# CH32F203C8T6-R1.net
KiCad netlist of a schematic drawn in Altium Designer
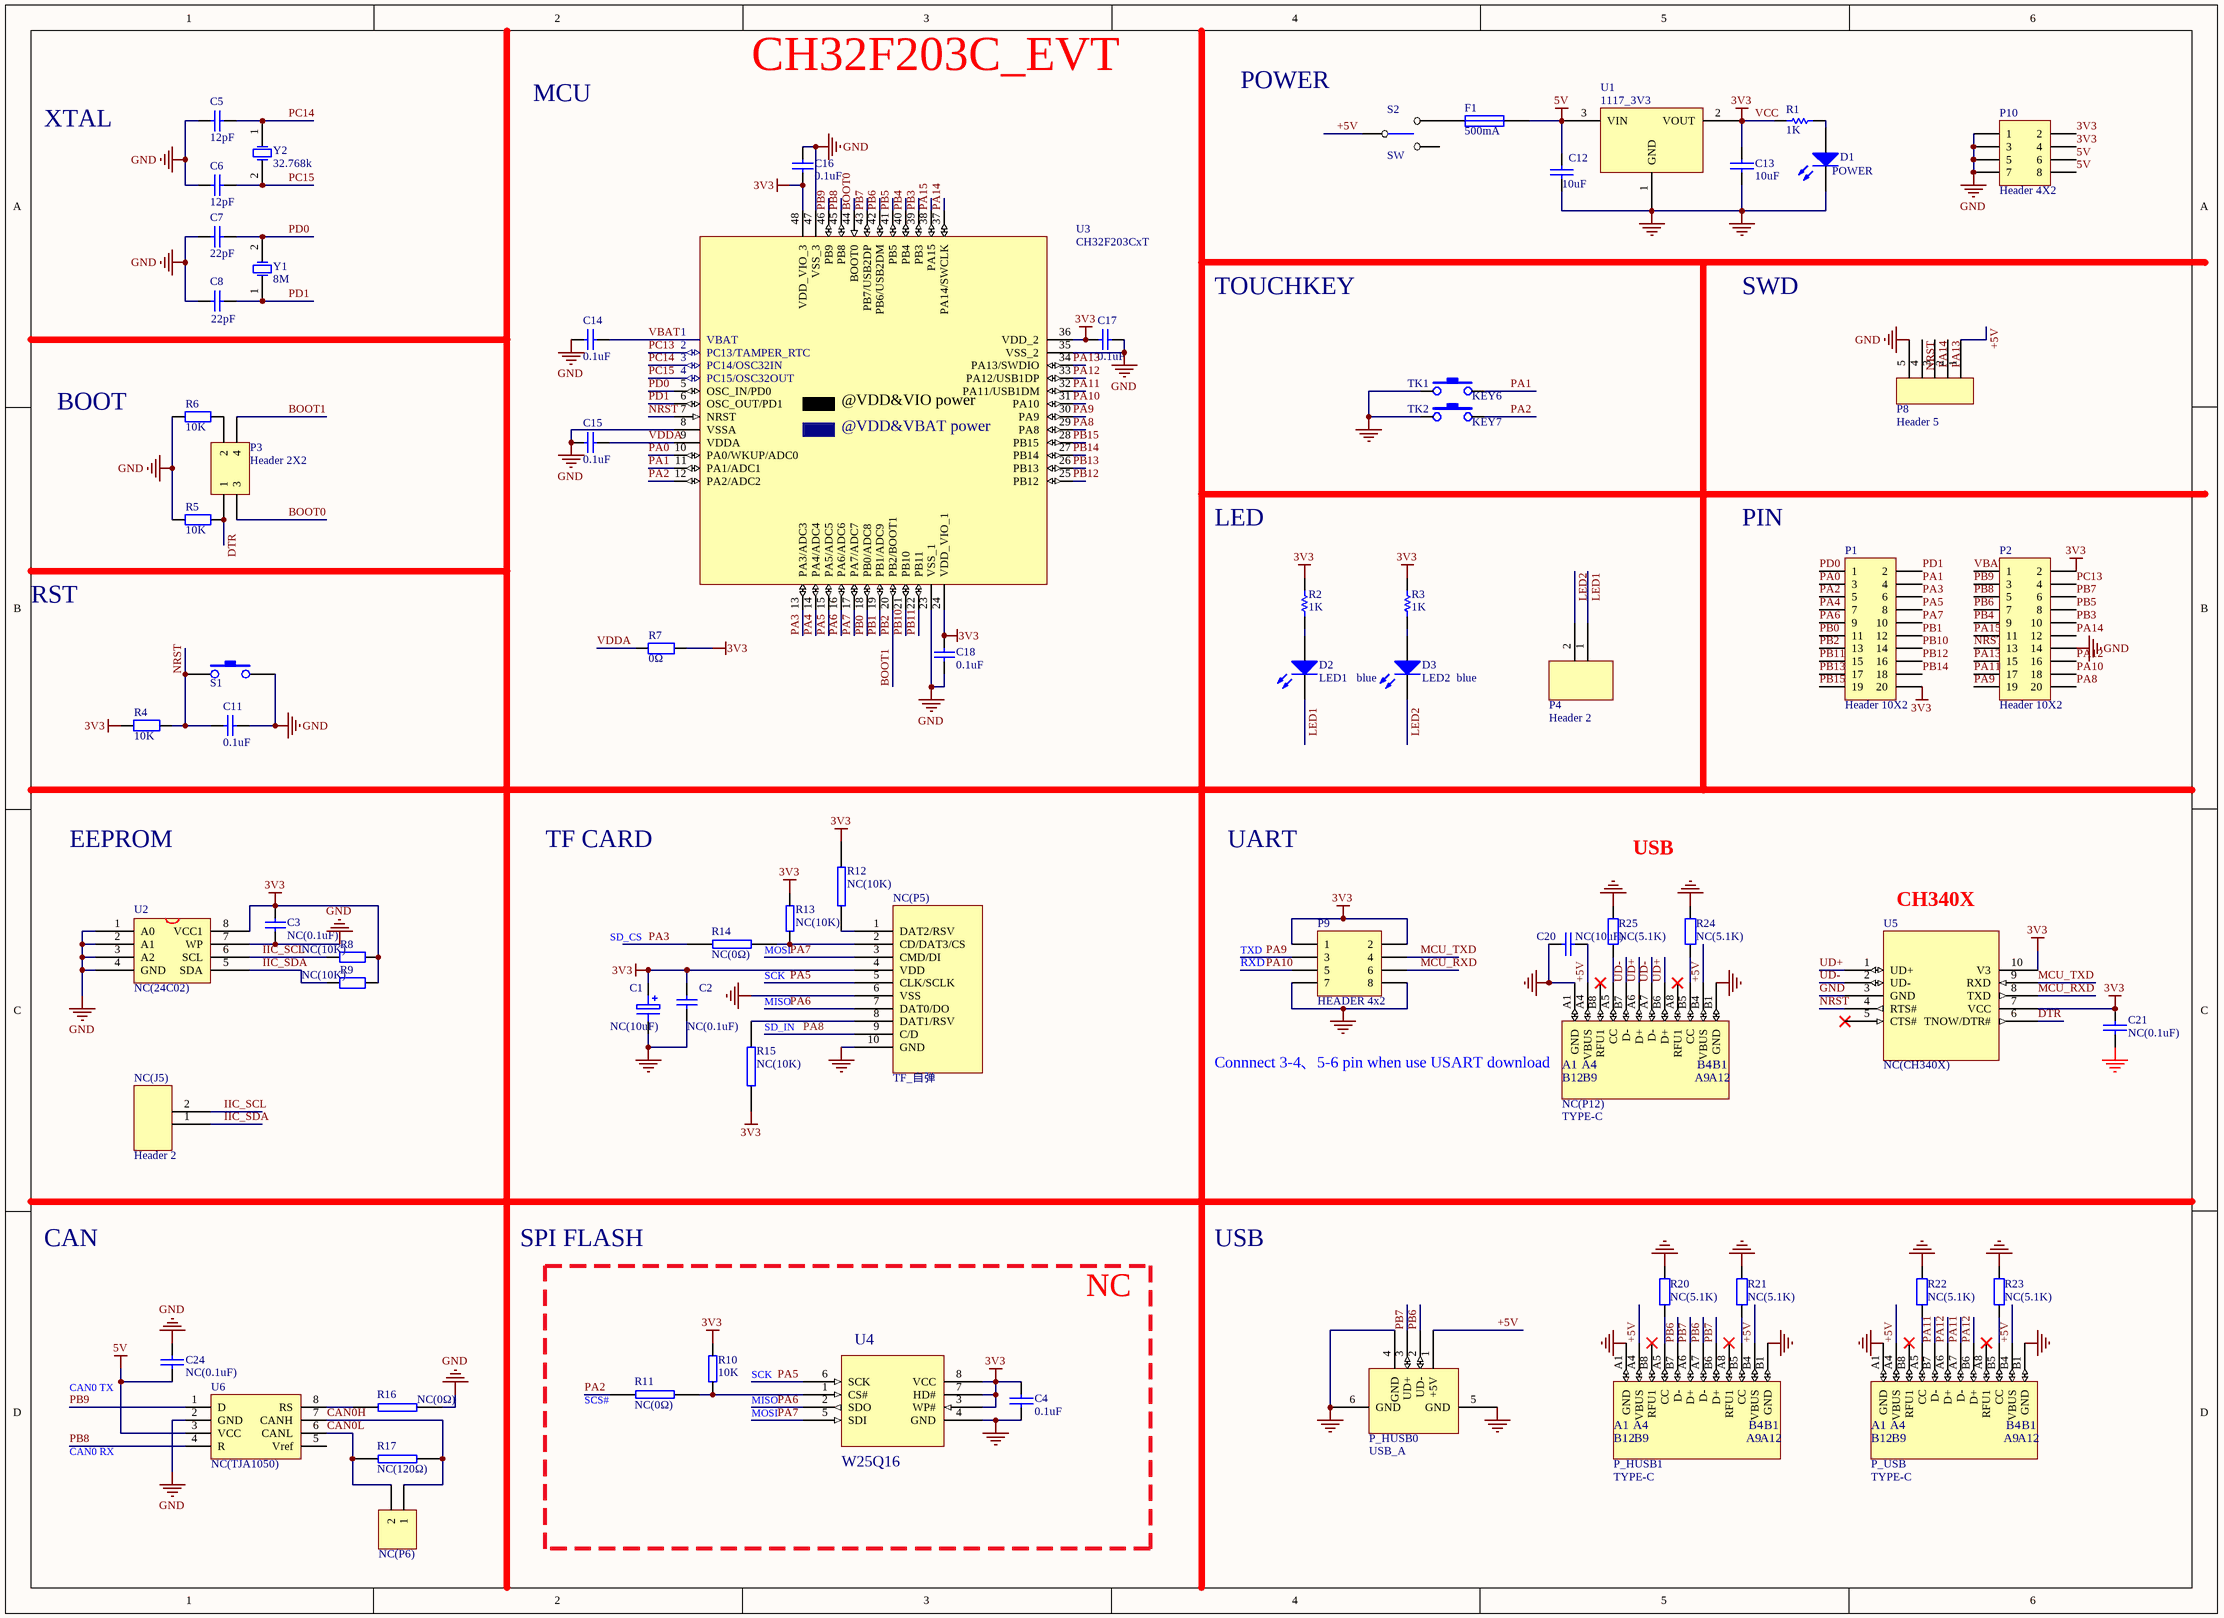
[diagram p0: CH32F203C8T6-R1.SchDoc]

(export (version "E")
  (design (tool "Eeschema 10.0.6"))
  (components
    (comp (ref "C1")
      (value "NC(10uF)")
      (footprint "3216")
      (description "Electrolytic Capacitor")
      (libsource (lib "*") (part "ELECTRO1"))
    )
    (comp (ref "C2")
      (value "NC(0.1uF)")
      (footprint "0603")
      (description "Capacitor")
      (fields (field (name "Comment") "0.1uF") (field (name "PUBLISHER") "Altium Limited"))
      (libsource (lib "*") (part "Cap"))
    )
    (comp (ref "C3")
      (value "NC(0.1uF)")
      (footprint "0603")
      (description "Capacitor")
      (fields (field (name "PUBLISHER") "Altium Limited"))
      (libsource (lib "Miscellaneous Devices") (part "Cap"))
    )
    (comp (ref "C4")
      (value "0.1uF")
      (footprint "0603")
      (description "Capacitor")
      (libsource (lib "") (part "CAP_1"))
    )
    (comp (ref "C5")
      (value "12pF")
      (footprint "0603")
      (description "Capacitor")
      (fields (field (name "PUBLISHER") "Altium Limited"))
      (libsource (lib "Miscellaneous Devices") (part "Cap"))
    )
    (comp (ref "C6")
      (value "12pF")
      (footprint "0603")
      (description "Capacitor")
      (fields (field (name "PUBLISHER") "Altium Limited"))
      (libsource (lib "Miscellaneous Devices") (part "Cap"))
    )
    (comp (ref "C7")
      (value "22pF")
      (footprint "0603")
      (description "Capacitor")
      (fields (field (name "PUBLISHER") "Altium Limited"))
      (libsource (lib "Miscellaneous Devices") (part "Cap"))
    )
    (comp (ref "C8")
      (value "22pF")
      (footprint "0603")
      (description "Capacitor")
      (fields (field (name "PUBLISHER") "Altium Limited"))
      (libsource (lib "Miscellaneous Devices") (part "Cap"))
    )
    (comp (ref "C11")
      (value "0.1uF")
      (footprint "0603")
      (description "Capacitor")
      (fields (field (name "PUBLISHER") "Altium Limited"))
      (libsource (lib "Miscellaneous Devices") (part "Cap"))
    )
    (comp (ref "C12")
      (value "10uF")
      (footprint "3216")
      (description "Capacitor")
      (libsource (lib "*") (part "CAP"))
    )
    (comp (ref "C13")
      (value "10uF")
      (footprint "0603")
      (description "Capacitor")
      (libsource (lib "*") (part "CAP"))
    )
    (comp (ref "C14")
      (value "0.1uF")
      (footprint "0603")
      (description "Capacitor")
      (fields (field (name "PUBLISHER") "Altium Limited"))
      (libsource (lib "Miscellaneous Devices") (part "Cap"))
    )
    (comp (ref "C15")
      (value "0.1uF")
      (footprint "0603")
      (description "Capacitor")
      (fields (field (name "PUBLISHER") "Altium Limited"))
      (libsource (lib "Miscellaneous Devices") (part "Cap"))
    )
    (comp (ref "C16")
      (value "0.1uF")
      (footprint "0603")
      (description "Capacitor")
      (fields (field (name "PUBLISHER") "Altium Limited"))
      (libsource (lib "Miscellaneous Devices") (part "Cap"))
    )
    (comp (ref "C17")
      (value "0.1uF")
      (footprint "0603")
      (description "Capacitor")
      (fields (field (name "PUBLISHER") "Altium Limited"))
      (libsource (lib "Miscellaneous Devices") (part "Cap"))
    )
    (comp (ref "C18")
      (value "0.1uF")
      (footprint "0603")
      (description "Capacitor")
      (fields (field (name "PUBLISHER") "Altium Limited"))
      (libsource (lib "Miscellaneous Devices") (part "Cap"))
    )
    (comp (ref "C20")
      (value "NC(10uF)")
      (footprint "3216_C")
      (description "Capacitor")
      (libsource (lib "*") (part "CAP"))
    )
    (comp (ref "C21")
      (value "NC(0.1uF)")
      (footprint "0603_C")
      (description "Capacitor")
      (libsource (lib "*") (part "CAP"))
    )
    (comp (ref "C24")
      (value "NC(0.1uF)")
      (footprint "0603")
      (description "Capacitor")
      (libsource (lib "") (part "CAP_1"))
    )
    (comp (ref "D1")
      (value "POWER")
      (footprint "0603L")
      (description "Typical INFRARED GaAs LED")
      (fields (field (name "PUBLISHER") "Altium Limited"))
      (libsource (lib "Miscellaneous Devices") (part "LED0"))
    )
    (comp (ref "D2")
      (value "LED1   blue")
      (footprint "0603L")
      (description "Typical INFRARED GaAs LED")
      (fields (field (name "PUBLISHER") "Altium Limited"))
      (libsource (lib "Miscellaneous Devices") (part "LED0"))
    )
    (comp (ref "D3")
      (value "LED2  blue")
      (footprint "0603L")
      (description "Typical INFRARED GaAs LED")
      (fields (field (name "PUBLISHER") "Altium Limited"))
      (libsource (lib "Miscellaneous Devices") (part "LED0"))
    )
    (comp (ref "F1")
      (value "500mA")
      (footprint "0603")
      (description "Fuse")
      (libsource (lib "*") (part "FUSE1"))
    )
    (comp (ref "NC(J5)")
      (value "Header 2")
      (footprint "SIP2 - 40mil")
      (libsource (lib "MYSCH") (part "2HEAD"))
    )
    (comp (ref "NC(P5)") (value "TF_自弹") (footprint "TF_CARD") (libsource (lib "*") (part "TF_自弹")))
    (comp (ref "NC(P6)")
      (value "Header 2")
      (footprint "PORT2 4.5MM")
      (description "Header, 2-Pin")
      (fields (field (name "PUBLISHER") "Altium Limited"))
      (libsource (lib "Miscellaneous Connectors") (part "Header 2"))
    )
    (comp (ref "NC(P12)")
      (value "TYPE-C")
      (footprint "TYPE-C-Receptacle-2.0")
      (libsource (lib "*") (part "TYPE-C1"))
    )
    (comp (ref "P1")
      (value "Header 10X2")
      (footprint "IDC20")
      (description "Header, 10-Pin, Dual row")
      (fields (field (name "PUBLISHER") "Altium Limited"))
      (libsource (lib "Miscellaneous Connectors") (part "Header 10X2"))
    )
    (comp (ref "P2")
      (value "Header 10X2")
      (footprint "IDC20")
      (description "Header, 10-Pin, Dual row")
      (fields (field (name "PUBLISHER") "Altium Limited"))
      (libsource (lib "Miscellaneous Connectors") (part "Header 10X2"))
    )
    (comp (ref "P3")
      (value "Header 2X2")
      (footprint "HDR2X2")
      (description "Header, 2-Pin, Dual row")
      (fields (field (name "PUBLISHER") "Altium Limited"))
      (libsource (lib "Miscellaneous Connectors") (part "Header 2X2"))
    )
    (comp (ref "P4") (value "Header 2") (footprint "SIP2 - 40mil") (libsource (lib "") (part "2HEAD_1")))
    (comp (ref "P8")
      (value "Header 5")
      (footprint "SIP5 - 40mil")
      (libsource (lib "PCB_Project1") (part "2HEAD"))
    )
    (comp (ref "P9")
      (value "HEADER 4x2")
      (footprint "MYPCB:IDC8-2.54mm")
      (description "Header, 4-Pin, Dual row")
      (libsource (lib "wch_sch_others") (part "HEADER 4x2"))
    )
    (comp (ref "P10")
      (value "Header 4X2")
      (footprint "IDC8")
      (description "Header, 4-Pin, Dual row")
      (fields (field (name "PUBLISHER") "Altium Limited"))
      (libsource (lib "Miscellaneous Connectors") (part "Header 4X2"))
    )
    (comp (ref "P_HUSB0")
      (value "USB_A")
      (footprint "USBA-l")
      (description "USB Port")
      (libsource (lib "CHXXXSCH") (part "USB"))
    )
    (comp (ref "P_HUSB1")
      (value "TYPE-C")
      (footprint "TYPE-C-Receptacle-2.0")
      (libsource (lib "*") (part "TYPE-C1"))
    )
    (comp (ref "P_USB")
      (value "TYPE-C")
      (footprint "TYPE-C-Receptacle-2.0")
      (libsource (lib "*") (part "TYPE-C1"))
    )
    (comp (ref "R1")
      (value "1K")
      (footprint "0603")
      (description "Semiconductor Resistor")
      (fields (field (name "PUBLISHER") "Altium Limited"))
      (libsource (lib "Miscellaneous Devices") (part "Res Semi"))
    )
    (comp (ref "R2")
      (value "1K")
      (footprint "0603")
      (description "Semiconductor Resistor")
      (fields (field (name "PUBLISHER") "Altium Limited"))
      (libsource (lib "Miscellaneous Devices") (part "Res Semi"))
    )
    (comp (ref "R3")
      (value "1K")
      (footprint "0603")
      (description "Semiconductor Resistor")
      (fields (field (name "PUBLISHER") "Altium Limited"))
      (libsource (lib "Miscellaneous Devices") (part "Res Semi"))
    )
    (comp (ref "R4")
      (value "10K")
      (footprint "0603")
      (description "Resistor")
      (fields (field (name "PUBLISHER") "Altium Limited"))
      (libsource (lib "Miscellaneous Devices") (part "Res2"))
    )
    (comp (ref "R5")
      (value "10K")
      (footprint "0603")
      (description "Resistor")
      (fields (field (name "PUBLISHER") "Altium Limited"))
      (libsource (lib "Miscellaneous Devices") (part "Res2"))
    )
    (comp (ref "R6")
      (value "10K")
      (footprint "0603")
      (description "Resistor")
      (fields (field (name "PUBLISHER") "Altium Limited"))
      (libsource (lib "Miscellaneous Devices") (part "Res2"))
    )
    (comp (ref "R7")
      (value "0Ω")
      (footprint "0603")
      (description "Resistor")
      (fields (field (name "PUBLISHER") "Altium Limited"))
      (libsource (lib "Miscellaneous Devices") (part "Res2"))
    )
    (comp (ref "R8")
      (value "NC(10K)")
      (footprint "0603")
      (description "Resistor")
      (fields (field (name "PUBLISHER") "Altium Limited"))
      (libsource (lib "Miscellaneous Devices") (part "Res2"))
    )
    (comp (ref "R9")
      (value "NC(10K)")
      (footprint "0603")
      (description "Resistor")
      (fields (field (name "PUBLISHER") "Altium Limited"))
      (libsource (lib "Miscellaneous Devices") (part "Res2"))
    )
    (comp (ref "R10") (value "10K") (footprint "0603") (libsource (lib "*") (part "DZ")))
    (comp (ref "R11") (value "NC(0Ω)") (footprint "0603") (libsource (lib "*") (part "RES2")))
    (comp (ref "R12") (value "NC(10K)") (footprint "0603") (libsource (lib "*") (part "RES2")))
    (comp (ref "R13") (value "NC(10K)") (footprint "0603") (libsource (lib "*") (part "DZ")))
    (comp (ref "R14") (value "NC(0Ω)") (footprint "0603") (libsource (lib "*") (part "RES2")))
    (comp (ref "R15") (value "NC(10K)") (footprint "0603") (libsource (lib "*") (part "RES2")))
    (comp (ref "R16") (value "NC(0Ω)") (footprint "0603") (libsource (lib "*") (part "RES2")))
    (comp (ref "R17") (value "NC(120Ω)") (footprint "0603") (libsource (lib "*") (part "RES2")))
    (comp (ref "R20")
      (value "NC(5.1K)")
      (footprint "0603")
      (description "Resistor")
      (libsource (lib "") (part "Res2_1"))
    )
    (comp (ref "R21")
      (value "NC(5.1K)")
      (footprint "0603")
      (description "Resistor")
      (libsource (lib "") (part "Res2_1"))
    )
    (comp (ref "R22")
      (value "NC(5.1K)")
      (footprint "0603")
      (description "Resistor")
      (libsource (lib "") (part "Res2_1"))
    )
    (comp (ref "R23")
      (value "NC(5.1K)")
      (footprint "0603")
      (description "Resistor")
      (libsource (lib "") (part "Res2_1"))
    )
    (comp (ref "R24")
      (value "NC(5.1K)")
      (footprint "0603")
      (description "Resistor")
      (libsource (lib "") (part "Res2_1"))
    )
    (comp (ref "R25")
      (value "NC(5.1K)")
      (footprint "0603")
      (description "Resistor")
      (libsource (lib "") (part "Res2_1"))
    )
    (comp (ref "S1") (value "KEY") (footprint "贴片按键") (libsource (lib "CCDXPLIB") (part "KEY")))
    (comp (ref "S2") (value "SW") (footprint "KEY2") (libsource (lib "MYSCH") (part "SW")))
    (comp (ref "TK1") (value "KEY6") (footprint "KEY68") (libsource (lib "*") (part "KEY")))
    (comp (ref "TK2") (value "KEY7") (footprint "KEY68") (libsource (lib "*") (part "KEY")))
    (comp (ref "U1") (value "1117_3V3") (footprint "SOT-223") (libsource (lib "*") (part "LM1117_3.3V")))
    (comp (ref "U2") (value "NC(24C02)") (footprint "SOP8") (libsource (lib "Elite_SCH") (part "24C256")))
    (comp (ref "U3")
      (value "CH32F203CxT")
      (footprint "LQFP48")
      (description "ARM M3 LMD-MCU, 144MHz, 2*USB FS, CAN")
      (libsource (lib "CHXXX") (part "CH32F203CxT"))
    )
    (comp (ref "U4")
      (value "W25Q16")
      (footprint "016 SO-8")
      (libsource (lib "*") (part "Pro89C.tmp_25F512_2"))
    )
    (comp (ref "U5")
      (value "NC(CH340X)")
      (footprint "MSOP10")
      (description "USB to TTL Serial / UART")
      (libsource (lib "CHXXX") (part "CH340X"))
    )
    (comp (ref "U6") (value "NC(TJA1050)") (footprint "SOP8") (libsource (lib "CAN") (part "Component_1")))
    (comp (ref "Y1")
      (value "8M")
      (footprint "XT62/28")
      (description "Crystal Oscillator")
      (fields (field (name "PUBLISHER") "Altium Limited"))
      (libsource (lib "Miscellaneous Devices") (part "XTAL"))
    )
    (comp (ref "Y2")
      (value "32.768k")
      (footprint "FC-135")
      (description "Crystal Oscillator")
      (fields (field (name "PUBLISHER") "Altium Limited"))
      (libsource (lib "Miscellaneous Devices") (part "XTAL"))
    )
  )
  (nets
    (net (code "1") (name "/+5V") (class "Default")
      (node (ref "C20") (pin "2") (pinfunction "2_2") (pintype "passive"))
      (node (ref "NC(P12)") (pin "A4") (pinfunction "VBUS_A4") (pintype "bidirectional"))
      (node (ref "NC(P12)") (pin "B4") (pinfunction "VBUS_B4") (pintype "bidirectional"))
      (node (ref "P8") (pin "1") (pintype "passive"))
      (node (ref "P_HUSB0") (pin "1") (pinfunction "+5V_1") (pintype "power_in"))
      (node (ref "P_HUSB1") (pin "A4") (pinfunction "VBUS_A4") (pintype "bidirectional"))
      (node (ref "P_HUSB1") (pin "B4") (pinfunction "VBUS_B4") (pintype "bidirectional"))
      (node (ref "P_USB") (pin "A4") (pinfunction "VBUS_A4") (pintype "bidirectional"))
      (node (ref "P_USB") (pin "B4") (pinfunction "VBUS_B4") (pintype "bidirectional"))
      (node (ref "S2") (pin "1") (pinfunction "1_1") (pintype "passive"))
    )
    (net (code "3") (name "/BOOT0") (class "Default")
      (node (ref "P3") (pin "3") (pinfunction "3_3") (pintype "passive"))
      (node (ref "U3") (pin "44") (pinfunction "BOOT0_44") (pintype "input"))
    )
    (net (code "4") (name "/BOOT1") (class "Default")
      (node (ref "P1") (pin "13") (pinfunction "13_13") (pintype "passive"))
      (node (ref "P3") (pin "4") (pinfunction "4_4") (pintype "passive"))
      (node (ref "U3") (pin "20") (pinfunction "PB2/BOOT1_20") (pintype "bidirectional"))
    )
    (net (code "5") (name "/CAN0H") (class "Default")
      (node (ref "NC(P6)") (pin "1") (pinfunction "1_1") (pintype "passive"))
      (node (ref "R17") (pin "1") (pinfunction "1_1") (pintype "passive"))
      (node (ref "U6") (pin "7") (pinfunction "CANH_7") (pintype "passive"))
    )
    (net (code "6") (name "/CAN0L") (class "Default")
      (node (ref "NC(P6)") (pin "2") (pinfunction "2_2") (pintype "passive"))
      (node (ref "R17") (pin "2") (pinfunction "2_2") (pintype "passive"))
      (node (ref "U6") (pin "6") (pinfunction "CANL_6") (pintype "passive"))
    )
    (net (code "7") (name "/DTR") (class "Default")
      (node (ref "P3") (pin "1") (pinfunction "1_1") (pintype "passive"))
      (node (ref "R5") (pin "1") (pinfunction "1_1") (pintype "passive"))
      (node (ref "U5") (pin "6") (pinfunction "TNOW/DTR#_6") (pintype "output"))
    )
    (net (code "8") (name "/IIC_SCL") (class "Default")
      (node (ref "NC(J5)") (pin "2") (pintype "passive"))
      (node (ref "R8") (pin "2") (pinfunction "2_2") (pintype "passive"))
      (node (ref "U2") (pin "6") (pinfunction "SCL_6") (pintype "passive"))
    )
    (net (code "9") (name "/IIC_SDA") (class "Default")
      (node (ref "NC(J5)") (pin "1") (pintype "passive"))
      (node (ref "R9") (pin "2") (pinfunction "2_2") (pintype "passive"))
      (node (ref "U2") (pin "5") (pinfunction "SDA_5") (pintype "passive"))
    )
    (net (code "10") (name "/LED1") (class "Default")
      (node (ref "D2") (pin "2") (pinfunction "K_2") (pintype "passive"))
      (node (ref "P4") (pin "1") (pintype "passive"))
    )
    (net (code "11") (name "/LED2") (class "Default")
      (node (ref "D3") (pin "2") (pinfunction "K_2") (pintype "passive"))
      (node (ref "P4") (pin "2") (pintype "passive"))
    )
    (net (code "12") (name "/MCU_RXD") (class "Default")
      (node (ref "P9") (pin "6") (pinfunction "6_6") (pintype "passive"))
      (node (ref "U5") (pin "8") (pinfunction "TXD_8") (pintype "output"))
    )
    (net (code "13") (name "/MCU_TXD") (class "Default")
      (node (ref "P9") (pin "4") (pinfunction "4_4") (pintype "passive"))
      (node (ref "U5") (pin "9") (pinfunction "RXD_9") (pintype "input"))
    )
    (net (code "14") (name "/NRST") (class "Default")
      (node (ref "C11") (pin "2") (pinfunction "2_2") (pintype "passive"))
      (node (ref "P2") (pin "13") (pinfunction "13_13") (pintype "passive"))
      (node (ref "P8") (pin "4") (pintype "passive"))
      (node (ref "R4") (pin "1") (pinfunction "1_1") (pintype "passive"))
      (node (ref "S1") (pin "1") (pinfunction "1_1") (pintype "passive"))
      (node (ref "U3") (pin "7") (pinfunction "NRST_7") (pintype "input"))
      (node (ref "U5") (pin "4") (pinfunction "RTS#_4") (pintype "output"))
    )
    (net (code "15") (name "/PA0") (class "Default")
      (node (ref "P1") (pin "3") (pinfunction "3_3") (pintype "passive"))
      (node (ref "U3") (pin "10") (pinfunction "PA0/WKUP/ADC0_10") (pintype "bidirectional"))
    )
    (net (code "16") (name "/PA1") (class "Default")
      (node (ref "P1") (pin "4") (pinfunction "4_4") (pintype "passive"))
      (node (ref "TK1") (pin "1") (pintype "passive"))
      (node (ref "U3") (pin "11") (pinfunction "PA1/ADC1_11") (pintype "bidirectional"))
    )
    (net (code "17") (name "/PA2") (class "Default")
      (node (ref "P1") (pin "5") (pinfunction "5_5") (pintype "passive"))
      (node (ref "R11") (pin "2") (pinfunction "2_2") (pintype "passive"))
      (node (ref "TK2") (pin "1") (pintype "passive"))
      (node (ref "U3") (pin "12") (pinfunction "PA2/ADC2_12") (pintype "bidirectional"))
    )
    (net (code "18") (name "/PA3") (class "Default")
      (node (ref "P1") (pin "6") (pinfunction "6_6") (pintype "passive"))
      (node (ref "R14") (pin "2") (pinfunction "2_2") (pintype "passive"))
      (node (ref "U3") (pin "13") (pinfunction "PA3/ADC3_13") (pintype "bidirectional"))
    )
    (net (code "19") (name "/PA4") (class "Default")
      (node (ref "P1") (pin "7") (pinfunction "7_7") (pintype "passive"))
      (node (ref "U3") (pin "14") (pinfunction "PA4/ADC4_14") (pintype "bidirectional"))
    )
    (net (code "20") (name "/PA5") (class "Default")
      (node (ref "NC(P5)") (pin "5") (pinfunction "CLK/SCLK_5") (pintype "passive"))
      (node (ref "P1") (pin "8") (pinfunction "8_8") (pintype "passive"))
      (node (ref "U3") (pin "15") (pinfunction "PA5/ADC5_15") (pintype "bidirectional"))
      (node (ref "U4") (pin "6") (pinfunction "SCK_6") (pintype "input"))
    )
    (net (code "21") (name "/PA6") (class "Default")
      (node (ref "NC(P5)") (pin "7") (pinfunction "DAT0/DO_7") (pintype "passive"))
      (node (ref "P1") (pin "9") (pinfunction "9_9") (pintype "passive"))
      (node (ref "U3") (pin "16") (pinfunction "PA6/ADC6_16") (pintype "bidirectional"))
      (node (ref "U4") (pin "2") (pinfunction "SDO_2") (pintype "output"))
    )
    (net (code "22") (name "/PA7") (class "Default")
      (node (ref "NC(P5)") (pin "3") (pinfunction "CMD/DI_3") (pintype "passive"))
      (node (ref "P1") (pin "10") (pinfunction "10_10") (pintype "passive"))
      (node (ref "U3") (pin "17") (pinfunction "PA7/ADC7_17") (pintype "bidirectional"))
      (node (ref "U4") (pin "5") (pinfunction "SDI_5") (pintype "input"))
    )
    (net (code "23") (name "/PA8") (class "Default")
      (node (ref "NC(P5)") (pin "9") (pinfunction "C/D_9") (pintype "passive"))
      (node (ref "P2") (pin "20") (pinfunction "20_20") (pintype "passive"))
      (node (ref "U3") (pin "29") (pinfunction "PA8_29") (pintype "bidirectional"))
    )
    (net (code "24") (name "/PA9") (class "Default")
      (node (ref "P2") (pin "19") (pinfunction "19_19") (pintype "passive"))
      (node (ref "P9") (pin "3") (pinfunction "3_3") (pintype "passive"))
      (node (ref "U3") (pin "30") (pinfunction "PA9_30") (pintype "bidirectional"))
    )
    (net (code "25") (name "/PA10") (class "Default")
      (node (ref "P2") (pin "18") (pinfunction "18_18") (pintype "passive"))
      (node (ref "P9") (pin "5") (pinfunction "5_5") (pintype "passive"))
      (node (ref "U3") (pin "31") (pinfunction "PA10_31") (pintype "bidirectional"))
    )
    (net (code "26") (name "/PA11") (class "Default")
      (node (ref "P2") (pin "17") (pinfunction "17_17") (pintype "passive"))
      (node (ref "P_USB") (pin "A7") (pinfunction "D-_A7") (pintype "bidirectional"))
      (node (ref "P_USB") (pin "B7") (pinfunction "D-_B7") (pintype "bidirectional"))
      (node (ref "U3") (pin "32") (pinfunction "PA11/USB1DM_32") (pintype "bidirectional"))
    )
    (net (code "27") (name "/PA12") (class "Default")
      (node (ref "P2") (pin "16") (pinfunction "16_16") (pintype "passive"))
      (node (ref "P_USB") (pin "A6") (pinfunction "D+_A6") (pintype "bidirectional"))
      (node (ref "P_USB") (pin "B6") (pinfunction "D+_B6") (pintype "bidirectional"))
      (node (ref "U3") (pin "33") (pinfunction "PA12/USB1DP_33") (pintype "bidirectional"))
    )
    (net (code "28") (name "/PA13") (class "Default")
      (node (ref "P2") (pin "15") (pinfunction "15_15") (pintype "passive"))
      (node (ref "P8") (pin "2") (pintype "passive"))
      (node (ref "U3") (pin "34") (pinfunction "PA13/SWDIO_34") (pintype "bidirectional"))
    )
    (net (code "29") (name "/PA14") (class "Default")
      (node (ref "P2") (pin "12") (pinfunction "12_12") (pintype "passive"))
      (node (ref "P8") (pin "3") (pintype "passive"))
      (node (ref "U3") (pin "37") (pinfunction "PA14/SWCLK_37") (pintype "bidirectional"))
    )
    (net (code "30") (name "/PA15") (class "Default")
      (node (ref "P2") (pin "11") (pinfunction "11_11") (pintype "passive"))
      (node (ref "U3") (pin "38") (pinfunction "PA15_38") (pintype "bidirectional"))
    )
    (net (code "31") (name "/PB0") (class "Default")
      (node (ref "P1") (pin "11") (pinfunction "11_11") (pintype "passive"))
      (node (ref "U3") (pin "18") (pinfunction "PB0/ADC8_18") (pintype "bidirectional"))
    )
    (net (code "32") (name "/PB1") (class "Default")
      (node (ref "P1") (pin "12") (pinfunction "12_12") (pintype "passive"))
      (node (ref "U3") (pin "19") (pinfunction "PB1/ADC9_19") (pintype "bidirectional"))
    )
    (net (code "33") (name "/PB3") (class "Default")
      (node (ref "P2") (pin "10") (pinfunction "10_10") (pintype "passive"))
      (node (ref "U3") (pin "39") (pinfunction "PB3_39") (pintype "bidirectional"))
    )
    (net (code "34") (name "/PB4") (class "Default")
      (node (ref "P2") (pin "9") (pinfunction "9_9") (pintype "passive"))
      (node (ref "U3") (pin "40") (pinfunction "PB4_40") (pintype "bidirectional"))
    )
    (net (code "35") (name "/PB5") (class "Default")
      (node (ref "P2") (pin "8") (pinfunction "8_8") (pintype "passive"))
      (node (ref "U3") (pin "41") (pinfunction "PB5_41") (pintype "bidirectional"))
    )
    (net (code "36") (name "/PB6") (class "Default")
      (node (ref "P2") (pin "7") (pinfunction "7_7") (pintype "passive"))
      (node (ref "P_HUSB0") (pin "2") (pinfunction "UD-_2") (pintype "bidirectional"))
      (node (ref "P_HUSB1") (pin "A7") (pinfunction "D-_A7") (pintype "bidirectional"))
      (node (ref "P_HUSB1") (pin "B7") (pinfunction "D-_B7") (pintype "bidirectional"))
      (node (ref "U3") (pin "42") (pinfunction "PB6/USB2DM_42") (pintype "bidirectional"))
    )
    (net (code "37") (name "/PB7") (class "Default")
      (node (ref "P2") (pin "6") (pinfunction "6_6") (pintype "passive"))
      (node (ref "P_HUSB0") (pin "3") (pinfunction "UD+_3") (pintype "bidirectional"))
      (node (ref "P_HUSB1") (pin "A6") (pinfunction "D+_A6") (pintype "bidirectional"))
      (node (ref "P_HUSB1") (pin "B6") (pinfunction "D+_B6") (pintype "bidirectional"))
      (node (ref "U3") (pin "43") (pinfunction "PB7/USB2DP_43") (pintype "bidirectional"))
    )
    (net (code "38") (name "/PB8") (class "Default")
      (node (ref "P2") (pin "5") (pinfunction "5_5") (pintype "passive"))
      (node (ref "U3") (pin "45") (pinfunction "PB8_45") (pintype "bidirectional"))
      (node (ref "U6") (pin "4") (pinfunction "R_4") (pintype "passive"))
    )
    (net (code "39") (name "/PB9") (class "Default")
      (node (ref "P2") (pin "3") (pinfunction "3_3") (pintype "passive"))
      (node (ref "U3") (pin "46") (pinfunction "PB9_46") (pintype "bidirectional"))
      (node (ref "U6") (pin "1") (pinfunction "D_1") (pintype "passive"))
    )
    (net (code "40") (name "/PB10") (class "Default")
      (node (ref "P1") (pin "14") (pinfunction "14_14") (pintype "passive"))
      (node (ref "U3") (pin "21") (pinfunction "PB10_21") (pintype "bidirectional"))
    )
    (net (code "41") (name "/PB11") (class "Default")
      (node (ref "P1") (pin "15") (pinfunction "15_15") (pintype "passive"))
      (node (ref "U3") (pin "22") (pinfunction "PB11_22") (pintype "bidirectional"))
    )
    (net (code "42") (name "/PB12") (class "Default")
      (node (ref "P1") (pin "16") (pinfunction "16_16") (pintype "passive"))
      (node (ref "U3") (pin "25") (pinfunction "PB12_25") (pintype "bidirectional"))
    )
    (net (code "43") (name "/PB13") (class "Default")
      (node (ref "P1") (pin "17") (pinfunction "17_17") (pintype "passive"))
      (node (ref "U3") (pin "26") (pinfunction "PB13_26") (pintype "bidirectional"))
    )
    (net (code "44") (name "/PB14") (class "Default")
      (node (ref "P1") (pin "18") (pinfunction "18_18") (pintype "passive"))
      (node (ref "U3") (pin "27") (pinfunction "PB14_27") (pintype "bidirectional"))
    )
    (net (code "45") (name "/PB15") (class "Default")
      (node (ref "P1") (pin "19") (pinfunction "19_19") (pintype "passive"))
      (node (ref "U3") (pin "28") (pinfunction "PB15_28") (pintype "bidirectional"))
    )
    (net (code "46") (name "/PC13") (class "Default")
      (node (ref "P2") (pin "4") (pinfunction "4_4") (pintype "passive"))
      (node (ref "U3") (pin "2") (pinfunction "PC13/TAMPER_RTC_2") (pintype "bidirectional"))
    )
    (net (code "47") (name "/PC14") (class "Default")
      (node (ref "C5") (pin "1") (pinfunction "1_1") (pintype "passive"))
      (node (ref "U3") (pin "3") (pinfunction "PC14/OSC32IN_3") (pintype "bidirectional"))
      (node (ref "Y2") (pin "1") (pinfunction "OSC1_1") (pintype "passive"))
    )
    (net (code "48") (name "/PC15") (class "Default")
      (node (ref "C6") (pin "1") (pinfunction "1_1") (pintype "passive"))
      (node (ref "U3") (pin "4") (pinfunction "PC15/OSC32OUT_4") (pintype "bidirectional"))
      (node (ref "Y2") (pin "2") (pinfunction "OSC2_2") (pintype "passive"))
    )
    (net (code "49") (name "/PD0") (class "Default")
      (node (ref "C7") (pin "2") (pinfunction "2_2") (pintype "passive"))
      (node (ref "P1") (pin "1") (pinfunction "1_1") (pintype "passive"))
      (node (ref "U3") (pin "5") (pinfunction "OSC_IN/PD0_5") (pintype "bidirectional"))
      (node (ref "Y1") (pin "2") (pinfunction "OSC2_2") (pintype "passive"))
    )
    (net (code "50") (name "/PD1") (class "Default")
      (node (ref "C8") (pin "2") (pinfunction "2_2") (pintype "passive"))
      (node (ref "P1") (pin "2") (pinfunction "2_2") (pintype "passive"))
      (node (ref "U3") (pin "6") (pinfunction "OSC_OUT/PD1_6") (pintype "bidirectional"))
      (node (ref "Y1") (pin "1") (pinfunction "OSC1_1") (pintype "passive"))
    )
    (net (code "51") (name "/UD+") (class "Default")
      (node (ref "NC(P12)") (pin "A6") (pinfunction "D+_A6") (pintype "bidirectional"))
      (node (ref "NC(P12)") (pin "B6") (pinfunction "D+_B6") (pintype "bidirectional"))
      (node (ref "U5") (pin "1") (pinfunction "UD+_1") (pintype "bidirectional"))
    )
    (net (code "52") (name "/UD-") (class "Default")
      (node (ref "NC(P12)") (pin "A7") (pinfunction "D-_A7") (pintype "bidirectional"))
      (node (ref "NC(P12)") (pin "B7") (pinfunction "D-_B7") (pintype "bidirectional"))
      (node (ref "U5") (pin "2") (pinfunction "UD-_2") (pintype "bidirectional"))
    )
    (net (code "53") (name "/VBAT") (class "Default")
      (node (ref "C14") (pin "1") (pinfunction "1_1") (pintype "passive"))
      (node (ref "P2") (pin "1") (pinfunction "1_1") (pintype "passive"))
      (node (ref "U3") (pin "1") (pinfunction "VBAT_1") (pintype "power_in"))
    )
    (net (code "54") (name "/VDDA") (class "Default")
      (node (ref "C15") (pin "1") (pinfunction "1_1") (pintype "passive"))
      (node (ref "R7") (pin "2") (pinfunction "2_2") (pintype "passive"))
      (node (ref "U3") (pin "9") (pinfunction "VDDA_9") (pintype "power_in"))
    )
    (net (code "55") (name "3V3") (class "Default")
      (node (ref "C1") (pin "1") (pinfunction "1_1") (pintype "passive"))
      (node (ref "C13") (pin "1") (pinfunction "1_1") (pintype "passive"))
      (node (ref "C16") (pin "2") (pinfunction "2_2") (pintype "passive"))
      (node (ref "C17") (pin "2") (pinfunction "2_2") (pintype "passive"))
      (node (ref "C18") (pin "2") (pinfunction "2_2") (pintype "passive"))
      (node (ref "C2") (pin "1") (pinfunction "1_1") (pintype "passive"))
      (node (ref "C21") (pin "1") (pinfunction "1_1") (pintype "passive"))
      (node (ref "C3") (pin "2") (pinfunction "2_2") (pintype "passive"))
      (node (ref "C4") (pin "2") (pinfunction "2_2") (pintype "passive"))
      (node (ref "NC(P5)") (pin "4") (pinfunction "VDD_4") (pintype "passive"))
      (node (ref "P1") (pin "20") (pinfunction "20_20") (pintype "passive"))
      (node (ref "P10") (pin "2") (pinfunction "2_2") (pintype "passive"))
      (node (ref "P10") (pin "4") (pinfunction "4_4") (pintype "passive"))
      (node (ref "P2") (pin "2") (pinfunction "2_2") (pintype "passive"))
      (node (ref "P9") (pin "1") (pinfunction "1_1") (pintype "passive"))
      (node (ref "P9") (pin "2") (pinfunction "2_2") (pintype "passive"))
      (node (ref "R1") (pin "2") (pinfunction "2_2") (pintype "passive"))
      (node (ref "R10") (pin "2") (pintype "passive"))
      (node (ref "R12") (pin "2") (pinfunction "2_2") (pintype "passive"))
      (node (ref "R13") (pin "2") (pintype "passive"))
      (node (ref "R15") (pin "1") (pinfunction "1_1") (pintype "passive"))
      (node (ref "R2") (pin "1") (pinfunction "1_1") (pintype "passive"))
      (node (ref "R3") (pin "1") (pinfunction "1_1") (pintype "passive"))
      (node (ref "R4") (pin "2") (pinfunction "2_2") (pintype "passive"))
      (node (ref "R7") (pin "1") (pinfunction "1_1") (pintype "passive"))
      (node (ref "R8") (pin "1") (pinfunction "1_1") (pintype "passive"))
      (node (ref "R9") (pin "1") (pinfunction "1_1") (pintype "passive"))
      (node (ref "U1") (pin "2") (pinfunction "VOUT_2") (pintype "passive"))
      (node (ref "U2") (pin "8") (pinfunction "VCC1_8") (pintype "passive"))
      (node (ref "U3") (pin "24") (pinfunction "VDD_VIO_1_24") (pintype "power_in"))
      (node (ref "U3") (pin "36") (pinfunction "VDD_2_36") (pintype "power_in"))
      (node (ref "U3") (pin "48") (pinfunction "VDD_VIO_3_48") (pintype "power_in"))
      (node (ref "U4") (pin "3") (pinfunction "WP#_3") (pintype "input"))
      (node (ref "U4") (pin "7") (pinfunction "HD#_7") (pintype "power_in"))
      (node (ref "U4") (pin "8") (pinfunction "VCC_8") (pintype "power_in"))
      (node (ref "U5") (pin "10") (pinfunction "V3_10") (pintype "power_in"))
      (node (ref "U5") (pin "7") (pinfunction "VCC_7") (pintype "power_in"))
    )
    (net (code "56") (name "5V") (class "Default")
      (node (ref "C12") (pin "1") (pinfunction "1_1") (pintype "passive"))
      (node (ref "C24") (pin "2") (pinfunction "2_2") (pintype "passive"))
      (node (ref "F1") (pin "2") (pinfunction "2_2") (pintype "passive"))
      (node (ref "P10") (pin "6") (pinfunction "6_6") (pintype "passive"))
      (node (ref "P10") (pin "8") (pinfunction "8_8") (pintype "passive"))
      (node (ref "U1") (pin "3") (pinfunction "VIN_3") (pintype "passive"))
      (node (ref "U6") (pin "3") (pinfunction "VCC_3") (pintype "passive"))
    )
    (net (code "57") (name "GND") (class "Default")
      (node (ref "C1") (pin "2") (pinfunction "2_2") (pintype "passive"))
      (node (ref "C11") (pin "1") (pinfunction "1_1") (pintype "passive"))
      (node (ref "C12") (pin "2") (pinfunction "2_2") (pintype "passive"))
      (node (ref "C13") (pin "2") (pinfunction "2_2") (pintype "passive"))
      (node (ref "C14") (pin "2") (pinfunction "2_2") (pintype "passive"))
      (node (ref "C15") (pin "2") (pinfunction "2_2") (pintype "passive"))
      (node (ref "C16") (pin "1") (pinfunction "1_1") (pintype "passive"))
      (node (ref "C17") (pin "1") (pinfunction "1_1") (pintype "passive"))
      (node (ref "C18") (pin "1") (pinfunction "1_1") (pintype "passive"))
      (node (ref "C2") (pin "2") (pinfunction "2_2") (pintype "passive"))
      (node (ref "C20") (pin "1") (pinfunction "1_1") (pintype "passive"))
      (node (ref "C21") (pin "2") (pinfunction "2_2") (pintype "passive"))
      (node (ref "C24") (pin "1") (pinfunction "1_1") (pintype "passive"))
      (node (ref "C3") (pin "1") (pinfunction "1_1") (pintype "passive"))
      (node (ref "C4") (pin "1") (pinfunction "1_1") (pintype "passive"))
      (node (ref "C5") (pin "2") (pinfunction "2_2") (pintype "passive"))
      (node (ref "C6") (pin "2") (pinfunction "2_2") (pintype "passive"))
      (node (ref "C7") (pin "1") (pinfunction "1_1") (pintype "passive"))
      (node (ref "C8") (pin "1") (pinfunction "1_1") (pintype "passive"))
      (node (ref "D1") (pin "2") (pinfunction "K_2") (pintype "passive"))
      (node (ref "NC(P12)") (pin "A1") (pinfunction "GND_A1") (pintype "bidirectional"))
      (node (ref "NC(P12)") (pin "B1") (pinfunction "GND_B1") (pintype "bidirectional"))
      (node (ref "NC(P5)") (pin "10") (pinfunction "GND_10") (pintype "passive"))
      (node (ref "NC(P5)") (pin "6") (pinfunction "VSS_6") (pintype "passive"))
      (node (ref "P10") (pin "1") (pinfunction "1_1") (pintype "passive"))
      (node (ref "P10") (pin "3") (pinfunction "3_3") (pintype "passive"))
      (node (ref "P10") (pin "5") (pinfunction "5_5") (pintype "passive"))
      (node (ref "P10") (pin "7") (pinfunction "7_7") (pintype "passive"))
      (node (ref "P2") (pin "14") (pinfunction "14_14") (pintype "passive"))
      (node (ref "P8") (pin "5") (pintype "passive"))
      (node (ref "P9") (pin "7") (pinfunction "7_7") (pintype "passive"))
      (node (ref "P9") (pin "8") (pinfunction "8_8") (pintype "passive"))
      (node (ref "P_HUSB0") (pin "4") (pinfunction "GND_4") (pintype "power_in"))
      (node (ref "P_HUSB0") (pin "5") (pinfunction "GND_5") (pintype "power_in"))
      (node (ref "P_HUSB0") (pin "6") (pinfunction "GND_6") (pintype "power_in"))
      (node (ref "P_HUSB1") (pin "A1") (pinfunction "GND_A1") (pintype "bidirectional"))
      (node (ref "P_HUSB1") (pin "B1") (pinfunction "GND_B1") (pintype "bidirectional"))
      (node (ref "P_USB") (pin "A1") (pinfunction "GND_A1") (pintype "bidirectional"))
      (node (ref "P_USB") (pin "B1") (pinfunction "GND_B1") (pintype "bidirectional"))
      (node (ref "R16") (pin "1") (pinfunction "1_1") (pintype "passive"))
      (node (ref "R20") (pin "2") (pinfunction "2_2") (pintype "passive"))
      (node (ref "R21") (pin "2") (pinfunction "2_2") (pintype "passive"))
      (node (ref "R22") (pin "2") (pinfunction "2_2") (pintype "passive"))
      (node (ref "R23") (pin "2") (pinfunction "2_2") (pintype "passive"))
      (node (ref "R24") (pin "2") (pinfunction "2_2") (pintype "passive"))
      (node (ref "R25") (pin "2") (pinfunction "2_2") (pintype "passive"))
      (node (ref "R5") (pin "2") (pinfunction "2_2") (pintype "passive"))
      (node (ref "R6") (pin "2") (pinfunction "2_2") (pintype "passive"))
      (node (ref "S1") (pin "3") (pinfunction "3_3") (pintype "passive"))
      (node (ref "TK1") (pin "3") (pintype "passive"))
      (node (ref "TK2") (pin "3") (pintype "passive"))
      (node (ref "U1") (pin "1") (pinfunction "GND_1") (pintype "passive"))
      (node (ref "U2") (pin "1") (pinfunction "A0_1") (pintype "passive"))
      (node (ref "U2") (pin "2") (pinfunction "A1_2") (pintype "passive"))
      (node (ref "U2") (pin "3") (pinfunction "A2_3") (pintype "passive"))
      (node (ref "U2") (pin "4") (pinfunction "GND_4") (pintype "passive"))
      (node (ref "U2") (pin "7") (pinfunction "WP_7") (pintype "passive"))
      (node (ref "U3") (pin "23") (pinfunction "VSS_1_23") (pintype "power_in"))
      (node (ref "U3") (pin "35") (pinfunction "VSS_2_35") (pintype "power_in"))
      (node (ref "U3") (pin "47") (pinfunction "VSS_3_47") (pintype "power_in"))
      (node (ref "U3") (pin "8") (pinfunction "VSSA_8") (pintype "power_in"))
      (node (ref "U4") (pin "4") (pinfunction "GND_4") (pintype "power_in"))
      (node (ref "U5") (pin "3") (pinfunction "GND_3") (pintype "power_in"))
      (node (ref "U6") (pin "2") (pinfunction "GND_2") (pintype "passive"))
    )
    (net (code "58") (name "Net-(D1-A)") (class "Default")
      (node (ref "D1") (pin "1") (pinfunction "A_1") (pintype "passive"))
      (node (ref "R1") (pin "1") (pinfunction "1_1") (pintype "passive"))
    )
    (net (code "59") (name "Net-(D2-A)") (class "Default")
      (node (ref "D2") (pin "1") (pinfunction "A_1") (pintype "passive"))
      (node (ref "R2") (pin "2") (pinfunction "2_2") (pintype "passive"))
    )
    (net (code "60") (name "Net-(D3-A)") (class "Default")
      (node (ref "D3") (pin "1") (pinfunction "A_1") (pintype "passive"))
      (node (ref "R3") (pin "2") (pinfunction "2_2") (pintype "passive"))
    )
    (net (code "61") (name "Net-(F1-Pad1)") (class "Default")
      (node (ref "F1") (pin "1") (pinfunction "1_1") (pintype "passive"))
      (node (ref "S2") (pin "2") (pinfunction "2_2") (pintype "passive"))
    )
    (net (code "62") (name "Net-(NC(P5)-CD{slash}DAT3{slash}CS)") (class "Default")
      (node (ref "NC(P5)") (pin "2") (pinfunction "CD/DAT3/CS_2") (pintype "passive"))
      (node (ref "R13") (pin "1") (pintype "passive"))
      (node (ref "R14") (pin "1") (pinfunction "1_1") (pintype "passive"))
    )
    (net (code "63") (name "Net-(NC(P5)-DAT1{slash}RSV)") (class "Default")
      (node (ref "NC(P5)") (pin "8") (pinfunction "DAT1/RSV_8") (pintype "passive"))
      (node (ref "R15") (pin "2") (pinfunction "2_2") (pintype "passive"))
    )
    (net (code "64") (name "Net-(NC(P5)-DAT2{slash}RSV)") (class "Default")
      (node (ref "NC(P5)") (pin "1") (pinfunction "DAT2/RSV_1") (pintype "passive"))
      (node (ref "R12") (pin "1") (pinfunction "1_1") (pintype "passive"))
    )
    (net (code "65") (name "Net-(NC(P12)-CC-PadA5)") (class "Default")
      (node (ref "NC(P12)") (pin "A5") (pinfunction "CC_A5") (pintype "bidirectional"))
      (node (ref "R25") (pin "1") (pinfunction "1_1") (pintype "passive"))
    )
    (net (code "66") (name "Net-(NC(P12)-CC-PadB5)") (class "Default")
      (node (ref "NC(P12)") (pin "B5") (pinfunction "CC_B5") (pintype "bidirectional"))
      (node (ref "R24") (pin "1") (pinfunction "1_1") (pintype "passive"))
    )
    (net (code "67") (name "Net-(P3-Pad2)") (class "Default")
      (node (ref "P3") (pin "2") (pinfunction "2_2") (pintype "passive"))
      (node (ref "R6") (pin "1") (pinfunction "1_1") (pintype "passive"))
    )
    (net (code "68") (name "Net-(P_HUSB1-CC-PadA5)") (class "Default")
      (node (ref "P_HUSB1") (pin "A5") (pinfunction "CC_A5") (pintype "bidirectional"))
      (node (ref "R20") (pin "1") (pinfunction "1_1") (pintype "passive"))
    )
    (net (code "69") (name "Net-(P_HUSB1-CC-PadB5)") (class "Default")
      (node (ref "P_HUSB1") (pin "B5") (pinfunction "CC_B5") (pintype "bidirectional"))
      (node (ref "R21") (pin "1") (pinfunction "1_1") (pintype "passive"))
    )
    (net (code "70") (name "Net-(P_USB-CC-PadA5)") (class "Default")
      (node (ref "P_USB") (pin "A5") (pinfunction "CC_A5") (pintype "bidirectional"))
      (node (ref "R22") (pin "1") (pinfunction "1_1") (pintype "passive"))
    )
    (net (code "71") (name "Net-(P_USB-CC-PadB5)") (class "Default")
      (node (ref "P_USB") (pin "B5") (pinfunction "CC_B5") (pintype "bidirectional"))
      (node (ref "R23") (pin "1") (pinfunction "1_1") (pintype "passive"))
    )
    (net (code "72") (name "Net-(U4-CS#)") (class "Default")
      (node (ref "R10") (pin "1") (pintype "passive"))
      (node (ref "R11") (pin "1") (pinfunction "1_1") (pintype "passive"))
      (node (ref "U4") (pin "1") (pinfunction "CS#_1") (pintype "input"))
    )
    (net (code "73") (name "Net-(U6-RS)") (class "Default")
      (node (ref "R16") (pin "2") (pinfunction "2_2") (pintype "passive"))
      (node (ref "U6") (pin "8") (pinfunction "RS_8") (pintype "passive"))
    )
    (net (code "74") (name "unconnected-(NC(P12)-RFU1-PadA8)") (class "Default")
      (node (ref "NC(P12)") (pin "A8") (pinfunction "RFU1_A8") (pintype "bidirectional+no_connect"))
    )
    (net (code "75") (name "unconnected-(NC(P12)-RFU1-PadB8)") (class "Default")
      (node (ref "NC(P12)") (pin "B8") (pinfunction "RFU1_B8") (pintype "bidirectional+no_connect"))
    )
    (net (code "76") (name "unconnected-(P_HUSB1-RFU1-PadA8)") (class "Default")
      (node (ref "P_HUSB1") (pin "A8") (pinfunction "RFU1_A8") (pintype "bidirectional+no_connect"))
    )
    (net (code "77") (name "unconnected-(P_HUSB1-RFU1-PadB8)") (class "Default")
      (node (ref "P_HUSB1") (pin "B8") (pinfunction "RFU1_B8") (pintype "bidirectional+no_connect"))
    )
    (net (code "78") (name "unconnected-(P_USB-RFU1-PadA8)") (class "Default")
      (node (ref "P_USB") (pin "A8") (pinfunction "RFU1_A8") (pintype "bidirectional+no_connect"))
    )
    (net (code "79") (name "unconnected-(P_USB-RFU1-PadB8)") (class "Default")
      (node (ref "P_USB") (pin "B8") (pinfunction "RFU1_B8") (pintype "bidirectional+no_connect"))
    )
    (net (code "80") (name "unconnected-(S2-Pad3)") (class "Default")
      (node (ref "S2") (pin "3") (pinfunction "3_3") (pintype "passive"))
    )
    (net (code "81") (name "unconnected-(U5-CTS#-Pad5)") (class "Default")
      (node (ref "U5") (pin "5") (pinfunction "CTS#_5") (pintype "input+no_connect"))
    )
    (net (code "82") (name "unconnected-(U6-Vref-Pad5)") (class "Default")
      (node (ref "U6") (pin "5") (pinfunction "Vref_5") (pintype "passive"))
    )
  )
)
